# Power_Sheet.net
KiCad netlist of a schematic drawn in Altium Designer
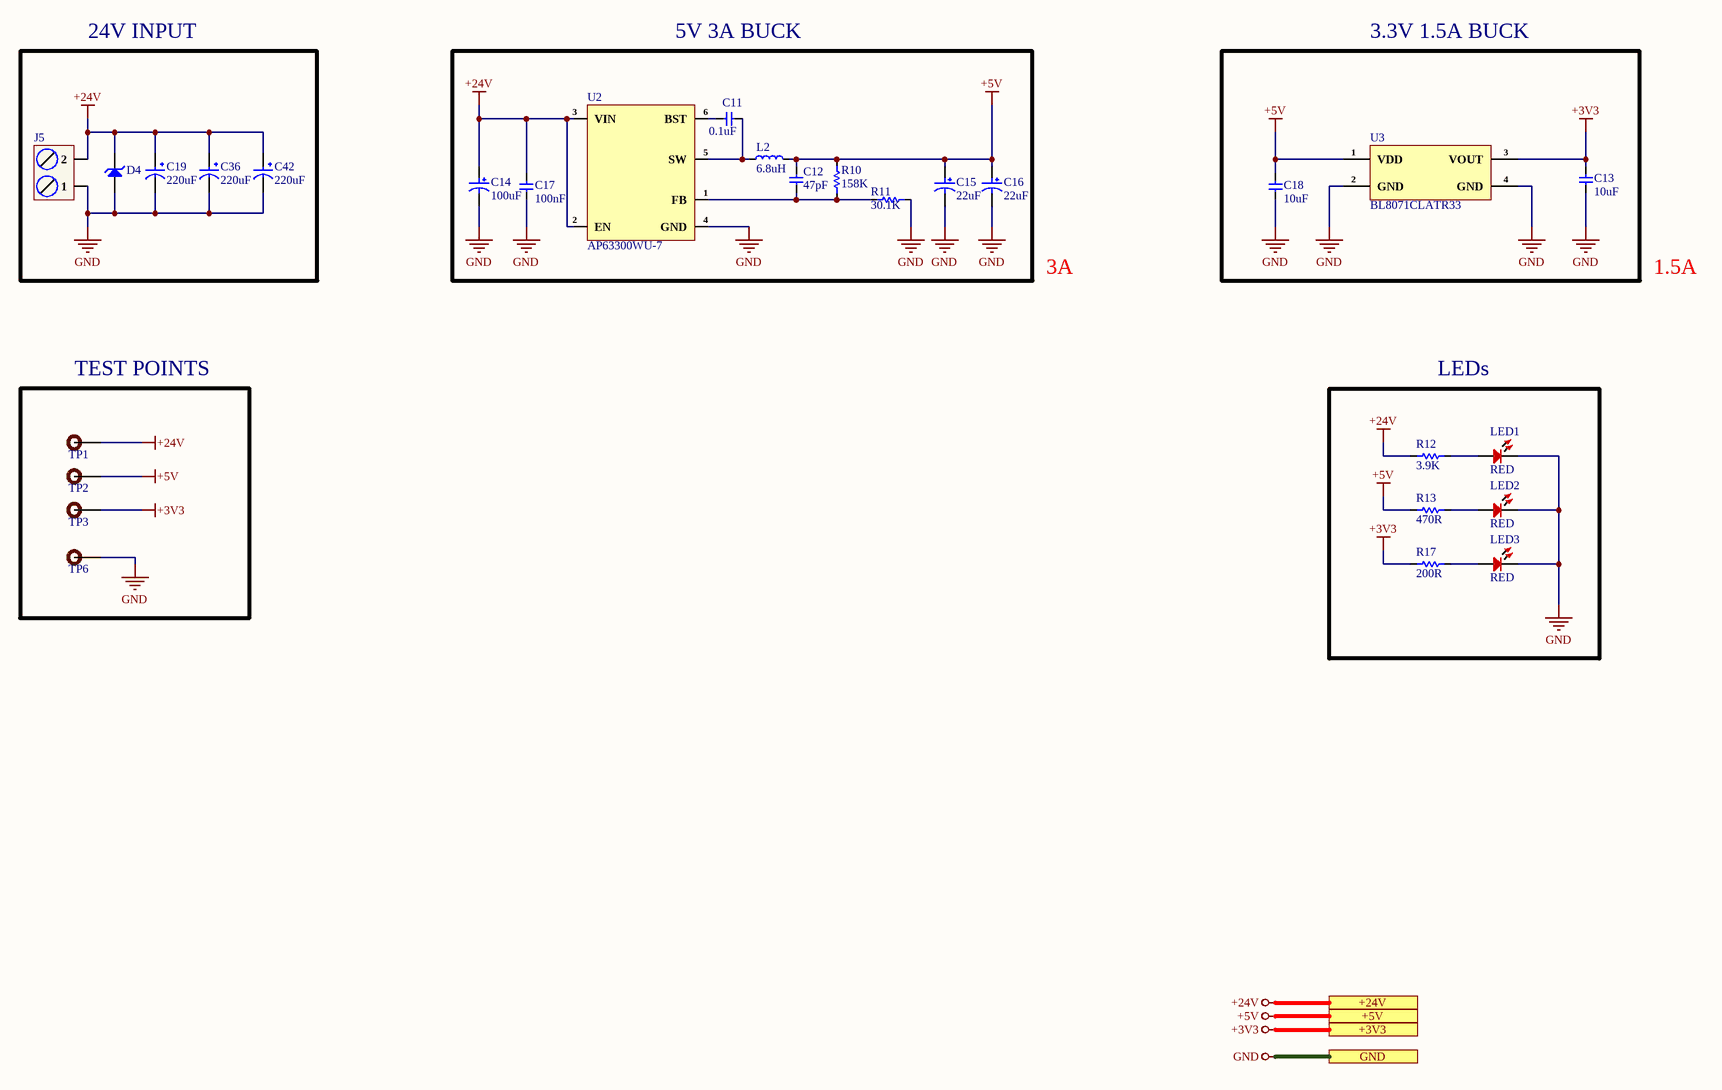
[diagram p0: Power_Sheet.SchDoc]

(export (version "E")
  (design (tool "Eeschema 10.0.6"))
  (components
    (comp (ref "C11")
      (value "0.1uF")
      (footprint "Cap-0402")
      (description "CAP CER 0.1UF 50V X5R 0402")
      (fields
        (field (name "MANUFACTURER") "TDK")
        (field (name "MANUFACTURER PART NUMBER") "C1005X5R1H104K050BB")
      )
      (libsource (lib "eSpark Libraries") (part "C1005X5R1H104K050BB"))
    )
    (comp (ref "C12")
      (value "47pF")
      (footprint "Cap-0402")
      (description "CAP CER 47PF 50V C0G/NP0 0402")
      (fields
        (field (name "MANUFACTURER") "Murata")
        (field (name "MANUFACTURER PART NUMBER") "GCM1555C1H470FA16D")
      )
      (libsource (lib "eSpark Libraries") (part "GCM1555C1H470FA16D"))
    )
    (comp (ref "C13")
      (value "10uF")
      (footprint "Cap-0603")
      (description "CAP CER 10UF 25V X5R 0603")
      (fields
        (field (name "MANUFACTURER") "TDK")
        (field (name "MANUFACTURER PART NUMBER") "C1608X5R1E106M080AC")
      )
      (libsource (lib "eSpark Libraries") (part "C1608X5R1E106M080AC"))
    )
    (comp (ref "C14")
      (value "100uF")
      (footprint "RVT1A101M0605")
      (description "100uF 10V 55mA@120Hz ±20% SMD,D6.3xL5.4mm Aluminum Electrolytic Capacitors - SMD ROHS")
      (fields
        (field (name "MANUFACTURER") "ROQANG")
        (field (name "MANUFACTURER PART NUMBER") "RVT1A101M0605")
      )
      (libsource (lib "eSpark Libraries") (part "RVT1A101M0605"))
    )
    (comp (ref "C15")
      (value "22uF")
      (footprint "VKMD1652D220MV")
      (description "22uF 200V 320mA@100kHz ±20% SMD,D8xL16.5mm Aluminum Electrolytic Capacitors - SMD ROHS")
      (fields (field (name "MANUFACTURER") "Ymin") (field (name "MANUFACTURER PART NUMBER") "VKMD1652D220MV"))
      (libsource (lib "eSpark Libraries") (part "VKMD1652D220MV"))
    )
    (comp (ref "C16")
      (value "22uF")
      (footprint "VKMD1652D220MV")
      (description "22uF 200V 320mA@100kHz ±20% SMD,D8xL16.5mm Aluminum Electrolytic Capacitors - SMD ROHS")
      (fields (field (name "MANUFACTURER") "Ymin") (field (name "MANUFACTURER PART NUMBER") "VKMD1652D220MV"))
      (libsource (lib "eSpark Libraries") (part "VKMD1652D220MV"))
    )
    (comp (ref "C17")
      (value "100nF")
      (footprint "cap-0402")
      (description "CAP CER 0.1UF 50V X7R 0402")
      (fields
        (field (name "MANUFACTURER") "TDK")
        (field (name "MANUFACTURER PART NUMBER") "C1005X7R1H104KT000F")
      )
      (libsource (lib "eSpark Libraries") (part "C1005X7R1H104KT000F"))
    )
    (comp (ref "C18")
      (value "10uF")
      (footprint "Cap-0603")
      (description "CAP CER 10UF 25V X5R 0603")
      (fields
        (field (name "MANUFACTURER") "TDK")
        (field (name "MANUFACTURER PART NUMBER") "C1608X5R1E106M080AC")
      )
      (libsource (lib "eSpark Libraries") (part "C1608X5R1E106M080AC"))
    )
    (comp (ref "C19")
      (value "220uF")
      (footprint "UCD-220uF-10mmDia")
      (description "CAP ALUM 220UF 20% 50V SMD")
      (fields
        (field (name "MANUFACTURER") "Nichicon")
        (field (name "MANUFACTURER PART NUMBER") "UCD1H221MNL1GS")
      )
      (libsource (lib "eSpark Libraries") (part "UCD1H221MNL1GS"))
    )
    (comp (ref "C36")
      (value "220uF")
      (footprint "UCD-220uF-10mmDia")
      (description "CAP ALUM 220UF 20% 50V SMD")
      (fields
        (field (name "MANUFACTURER") "Nichicon")
        (field (name "MANUFACTURER PART NUMBER") "UCD1H221MNL1GS")
      )
      (libsource (lib "eSpark Libraries") (part "UCD1H221MNL1GS"))
    )
    (comp (ref "C42")
      (value "220uF")
      (footprint "UCD-220uF-10mmDia")
      (description "CAP ALUM 220UF 20% 50V SMD")
      (fields
        (field (name "MANUFACTURER") "Nichicon")
        (field (name "MANUFACTURER PART NUMBER") "UCD1H221MNL1GS")
      )
      (libsource (lib "eSpark Libraries") (part "UCD1H221MNL1GS"))
    )
    (comp (ref "D4")
      (value "SMBJ28A-13-F")
      (footprint "SMB_")
      (description "TVS DIODE 28VWM 45.4VC SMB")
      (fields (field (name "MANUFACTURER") "Diodes"))
      (libsource (lib "eSpark Libraries") (part "SMBJ28A-13-F"))
    )
    (comp (ref "J5")
      (value "MXHB9500-9.5-02P-BK01-Cu-S-A")
      (footprint "MXHB9500-9.5-02P-BK01-Cu-S-A")
      (fields (field (name "MANUFACTURER") "MAX") (field (name "LCSC PART NUMBER") "C7542168"))
      (libsource (lib "eSpark Libraries") (part "MXHB9500-9.5-02P-BK01-Cu-S-A"))
    )
    (comp (ref "L2")
      (value "6.8uH")
      (footprint "LVC505040-6R8M-N_")
      (description "2.7A 6.8uH ±20% 50mΩ SMD Power Inductors ROHS")
      (fields
        (field (name "MANUFACTURER PART NUMBER") "LVC505040-6R8M-N")
        (field (name "MANUFACTURER") "Chlisin Elec")
      )
      (libsource (lib "eSpark Libraries") (part "LVC505040-6R8M-N"))
    )
    (comp (ref "LED1")
      (value "RED")
      (footprint "LED-0603")
      (description "RED LED 0603 Light Emitting Diodes")
      (fields
        (field (name "MANUFACTURER") "Foshan NationStar Optoelectronics")
        (field (name "MANUFACTURER PART NUMBER") "NCD0603R3")
      )
      (libsource (lib "eSpark Libraries") (part "NCD0603R3"))
    )
    (comp (ref "LED2")
      (value "RED")
      (footprint "LED-0603")
      (description "RED LED 0603 Light Emitting Diodes")
      (fields
        (field (name "MANUFACTURER") "Foshan NationStar Optoelectronics")
        (field (name "MANUFACTURER PART NUMBER") "NCD0603R3")
      )
      (libsource (lib "eSpark Libraries") (part "NCD0603R3"))
    )
    (comp (ref "LED3")
      (value "RED")
      (footprint "LED-0603")
      (description "RED LED 0603 Light Emitting Diodes")
      (fields
        (field (name "MANUFACTURER") "Foshan NationStar Optoelectronics")
        (field (name "MANUFACTURER PART NUMBER") "NCD0603R3")
      )
      (libsource (lib "eSpark Libraries") (part "NCD0603R3"))
    )
    (comp (ref "R10")
      (value "158K")
      (footprint "Res-0402")
      (description "RES 158K OHM 0.1% 1/16W 0402")
      (fields
        (field (name "MANUFACTURER") "Yageo")
        (field (name "MANUFACTURER PART NUMBER") "RT0402BRE07158KL")
      )
      (libsource (lib "eSpark Libraries") (part "RT0402BRE07158KL"))
    )
    (comp (ref "R11")
      (value "30.1K")
      (footprint "Res-0402")
      (description "RES SMD 30.1KOHM 0.1% 1/16W 0402")
      (fields
        (field (name "MANUFACTURER") "Yageo")
        (field (name "MANUFACTURER PART NUMBER") "RT0402BRD0730K1L")
      )
      (libsource (lib "eSpark Libraries") (part "RT0402BRD0730K1L"))
    )
    (comp (ref "R12")
      (value "3.9K")
      (footprint "Res-0402")
      (description "RES 3.9K OHM 1% 1/16W 0402")
      (fields
        (field (name "MANUFACTURER") "Yageo")
        (field (name "MANUFACTURER PART NUMBER") "RC0402FR-073K9L")
      )
      (libsource (lib "eSpark Libraries") (part "RC0402FR-073K9L"))
    )
    (comp (ref "R13")
      (value "470R")
      (footprint "Res-0402")
      (description "RES 470 OHM 1% 1/16W 0402")
      (fields
        (field (name "MANUFACTURER") "Yageo")
        (field (name "MANUFACTURER PART NUMBER") "RC0402FR-07470RL")
      )
      (libsource (lib "eSpark Libraries") (part "RC0402FR-07470RL"))
    )
    (comp (ref "R17")
      (value "200R")
      (footprint "Res-0402")
      (description "RES 200 OHM 1% 1/16W 0402")
      (fields
        (field (name "MANUFACTURER") "Yageo")
        (field (name "MANUFACTURER PART NUMBER") "RC0402FR-07200RL")
      )
      (libsource (lib "eSpark Libraries") (part "RC0402FR-07200RL"))
    )
    (comp (ref "TP1")
      (value "TEST POINT")
      (footprint "Test-point")
      (description "Test Point ON")
      (libsource (lib "eSpark Libraries") (part "TEST POINT"))
    )
    (comp (ref "TP2")
      (value "TEST POINT")
      (footprint "Test-point")
      (description "Test Point ON")
      (libsource (lib "eSpark Libraries") (part "TEST POINT"))
    )
    (comp (ref "TP3")
      (value "TEST POINT")
      (footprint "Test-point")
      (description "Test Point ON")
      (libsource (lib "eSpark Libraries") (part "TEST POINT"))
    )
    (comp (ref "TP6")
      (value "TEST POINT")
      (footprint "Test-point")
      (description "Test Point ON")
      (libsource (lib "eSpark Libraries") (part "TEST POINT"))
    )
    (comp (ref "U2")
      (value "AP63300WU-7")
      (footprint "SOT-23-6")
      (description "IC REG BUCK ADJ 3A TSOT26")
      (fields (field (name "MANUFACTURER") "Diodes") (field (name "LCSC PART NUMBER") "C2158012"))
      (libsource (lib "eSpark Libraries") (part "AP63300WU-7"))
    )
    (comp (ref "U3")
      (value "BL8071CLATR33")
      (footprint "SOT- 223")
      (description "70dB@(100Hz) 1.5A Fixed 3.3V~3.3V Positive 6V SOT-223 Linear Voltage Regulators (LDO) ROHS")
      (fields
        (field (name "MANUFACTURER") "BL(Shanghai Belling)")
        (field (name "LCSC PART NUMBER") "C401677")
      )
      (libsource (lib "eSpark Libraries") (part "BL8071CLATR33"))
    )
  )
  (nets
    (net (code "1") (name "+3V3") (class "Default")
      (node (ref "C13") (pin "2") (pinfunction "2_2") (pintype "passive"))
      (node (ref "R17") (pin "1") (pinfunction "1_1") (pintype "passive"))
      (node (ref "TP3") (pin "1") (pinfunction "1_1") (pintype "passive"))
      (node (ref "U3") (pin "3") (pinfunction "VOUT_3") (pintype "passive"))
    )
    (net (code "2") (name "+5V") (class "Default")
      (node (ref "C12") (pin "2") (pinfunction "2_2") (pintype "passive"))
      (node (ref "C15") (pin "1") (pintype "passive"))
      (node (ref "C16") (pin "1") (pintype "passive"))
      (node (ref "C18") (pin "2") (pinfunction "2_2") (pintype "passive"))
      (node (ref "L2") (pin "2") (pinfunction "2_2") (pintype "passive"))
      (node (ref "R10") (pin "2") (pinfunction "2_2") (pintype "passive"))
      (node (ref "R13") (pin "1") (pinfunction "1_1") (pintype "passive"))
      (node (ref "TP2") (pin "1") (pinfunction "1_1") (pintype "passive"))
      (node (ref "U3") (pin "1") (pinfunction "VDD_1") (pintype "passive"))
    )
    (net (code "3") (name "+24V") (class "Default")
      (node (ref "C14") (pin "1") (pintype "passive"))
      (node (ref "C17") (pin "2") (pinfunction "2_2") (pintype "passive"))
      (node (ref "C19") (pin "1") (pinfunction "1_1") (pintype "passive"))
      (node (ref "C36") (pin "1") (pinfunction "1_1") (pintype "passive"))
      (node (ref "C42") (pin "1") (pinfunction "1_1") (pintype "passive"))
      (node (ref "D4") (pin "2") (pinfunction "K_2") (pintype "passive"))
      (node (ref "J5") (pin "2") (pinfunction "2_2") (pintype "passive"))
      (node (ref "R12") (pin "1") (pinfunction "1_1") (pintype "passive"))
      (node (ref "TP1") (pin "1") (pinfunction "1_1") (pintype "passive"))
      (node (ref "U2") (pin "2") (pinfunction "EN_2") (pintype "passive"))
      (node (ref "U2") (pin "3") (pinfunction "VIN_3") (pintype "passive"))
    )
    (net (code "4") (name "GND") (class "Default")
      (node (ref "C13") (pin "1") (pinfunction "1_1") (pintype "passive"))
      (node (ref "C14") (pin "2") (pintype "passive"))
      (node (ref "C15") (pin "2") (pintype "passive"))
      (node (ref "C16") (pin "2") (pintype "passive"))
      (node (ref "C17") (pin "1") (pinfunction "1_1") (pintype "passive"))
      (node (ref "C18") (pin "1") (pinfunction "1_1") (pintype "passive"))
      (node (ref "C19") (pin "2") (pinfunction "2_2") (pintype "passive"))
      (node (ref "C36") (pin "2") (pinfunction "2_2") (pintype "passive"))
      (node (ref "C42") (pin "2") (pinfunction "2_2") (pintype "passive"))
      (node (ref "D4") (pin "1") (pinfunction "A_1") (pintype "passive"))
      (node (ref "J5") (pin "1") (pinfunction "1_1") (pintype "passive"))
      (node (ref "LED1") (pin "2") (pinfunction "2_2") (pintype "passive"))
      (node (ref "LED2") (pin "2") (pinfunction "2_2") (pintype "passive"))
      (node (ref "LED3") (pin "2") (pinfunction "2_2") (pintype "passive"))
      (node (ref "R11") (pin "2") (pinfunction "2_2") (pintype "passive"))
      (node (ref "TP6") (pin "1") (pinfunction "1_1") (pintype "passive"))
      (node (ref "U2") (pin "4") (pinfunction "GND_4") (pintype "passive"))
      (node (ref "U3") (pin "2") (pinfunction "GND_2") (pintype "passive"))
      (node (ref "U3") (pin "4") (pinfunction "GND_4") (pintype "passive"))
    )
    (net (code "5") (name "Net-(LED1-Pad1)") (class "Default")
      (node (ref "LED1") (pin "1") (pinfunction "1_1") (pintype "passive"))
      (node (ref "R12") (pin "2") (pinfunction "2_2") (pintype "passive"))
    )
    (net (code "6") (name "Net-(LED2-Pad1)") (class "Default")
      (node (ref "LED2") (pin "1") (pinfunction "1_1") (pintype "passive"))
      (node (ref "R13") (pin "2") (pinfunction "2_2") (pintype "passive"))
    )
    (net (code "7") (name "Net-(LED3-Pad1)") (class "Default")
      (node (ref "LED3") (pin "1") (pinfunction "1_1") (pintype "passive"))
      (node (ref "R17") (pin "2") (pinfunction "2_2") (pintype "passive"))
    )
    (net (code "8") (name "Net-(U2-BST)") (class "Default")
      (node (ref "C11") (pin "2") (pinfunction "2_2") (pintype "passive"))
      (node (ref "U2") (pin "6") (pinfunction "BST_6") (pintype "passive"))
    )
    (net (code "9") (name "Net-(U2-FB)") (class "Default")
      (node (ref "C12") (pin "1") (pinfunction "1_1") (pintype "passive"))
      (node (ref "R10") (pin "1") (pinfunction "1_1") (pintype "passive"))
      (node (ref "R11") (pin "1") (pinfunction "1_1") (pintype "passive"))
      (node (ref "U2") (pin "1") (pinfunction "FB_1") (pintype "passive"))
    )
    (net (code "10") (name "Net-(U2-SW)") (class "Default")
      (node (ref "C11") (pin "1") (pinfunction "1_1") (pintype "passive"))
      (node (ref "L2") (pin "1") (pinfunction "1_1") (pintype "passive"))
      (node (ref "U2") (pin "5") (pinfunction "SW_5") (pintype "passive"))
    )
  )
)
